# CON_CAN_DB9M.net
KiCad netlist of a schematic drawn in Altium Designer
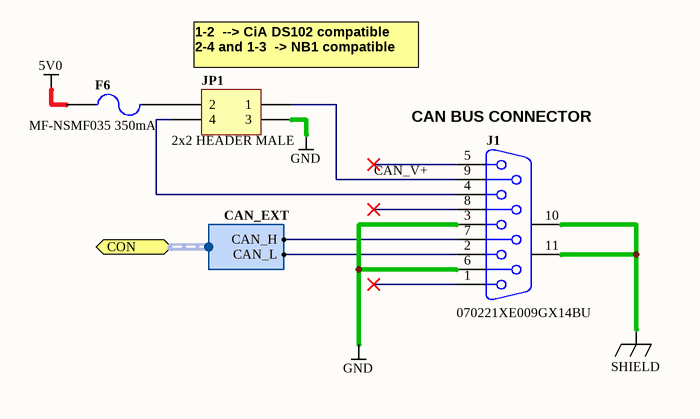
[diagram p0: CON_CAN_DB9M.SchDoc]

(export (version "E")
  (design (tool "Eeschema 10.0.6"))
  (components
    (comp (ref "F6")
      (value "MF-NSMF035 350mA")
      (footprint "RESC3216")
      (description "Multifuse, SMD 1206, 350mA")
      (libsource (lib "AltiumDesignLibrary") (part "MULTIFUSE"))
    )
    (comp (ref "J1")
      (value "070221XE009GX14BU")
      (footprint "070221XE009GX14BU")
      (description "Connector DB9 SMD Male/Pins; SUYIN")
      (libsource (lib "AltiumDesignLibrary") (part "CON-DB-9-M-RA"))
    )
    (comp (ref "JP1")
      (value "2x2 HEADER MALE")
      (footprint "HDR2X2")
      (description "Header IDC, 2 x 2 Pin Vertical 2.54mm Pitch (Non-Boxed, Male)")
      (libsource (lib "AltiumDesignLibrary") (part "CON-HDR-2x2-STR"))
    )
  )
  (nets
    (net (code "2") (name "/CAN_H") (class "Default")
      (node (ref "J1") (pin "7") (pinfunction "7_7") (pintype "passive"))
    )
    (net (code "3") (name "/CAN_L") (class "Default")
      (node (ref "J1") (pin "2") (pinfunction "2_2") (pintype "passive"))
    )
    (net (code "4") (name "/CAN_V+") (class "Default")
      (node (ref "J1") (pin "9") (pinfunction "9_9") (pintype "passive"))
      (node (ref "JP1") (pin "1") (pinfunction "1_1") (pintype "passive"))
    )
    (net (code "6") (name "5V0") (class "Default")
      (node (ref "F6") (pin "1") (pinfunction "1_1") (pintype "passive"))
    )
    (net (code "7") (name "GND") (class "Default")
      (node (ref "J1") (pin "3") (pinfunction "3_3") (pintype "passive"))
      (node (ref "J1") (pin "6") (pinfunction "6_6") (pintype "passive"))
      (node (ref "JP1") (pin "3") (pinfunction "3_3") (pintype "passive"))
    )
    (net (code "8") (name "Net-(F6-Pad2)") (class "Default")
      (node (ref "F6") (pin "2") (pinfunction "2_2") (pintype "passive"))
      (node (ref "JP1") (pin "2") (pinfunction "2_2") (pintype "passive"))
    )
    (net (code "9") (name "Net-(J1-Pad4)") (class "Default")
      (node (ref "J1") (pin "4") (pinfunction "4_4") (pintype "passive"))
      (node (ref "JP1") (pin "4") (pinfunction "4_4") (pintype "passive"))
    )
    (net (code "10") (name "SHIELD") (class "Default")
      (node (ref "J1") (pin "10") (pinfunction "MH1_10") (pintype "passive"))
      (node (ref "J1") (pin "11") (pinfunction "MH2_11") (pintype "passive"))
    )
    (net (code "11") (name "unconnected-(J1-Pad1)") (class "Default")
      (node (ref "J1") (pin "1") (pinfunction "1_1") (pintype "passive+no_connect"))
    )
    (net (code "12") (name "unconnected-(J1-Pad5)") (class "Default")
      (node (ref "J1") (pin "5") (pinfunction "5_5") (pintype "passive+no_connect"))
    )
    (net (code "13") (name "unconnected-(J1-Pad8)") (class "Default")
      (node (ref "J1") (pin "8") (pinfunction "8_8") (pintype "passive+no_connect"))
    )
  )
)
